# 15_SOLENOID_2.net
KiCad netlist of a schematic drawn in Altium Designer
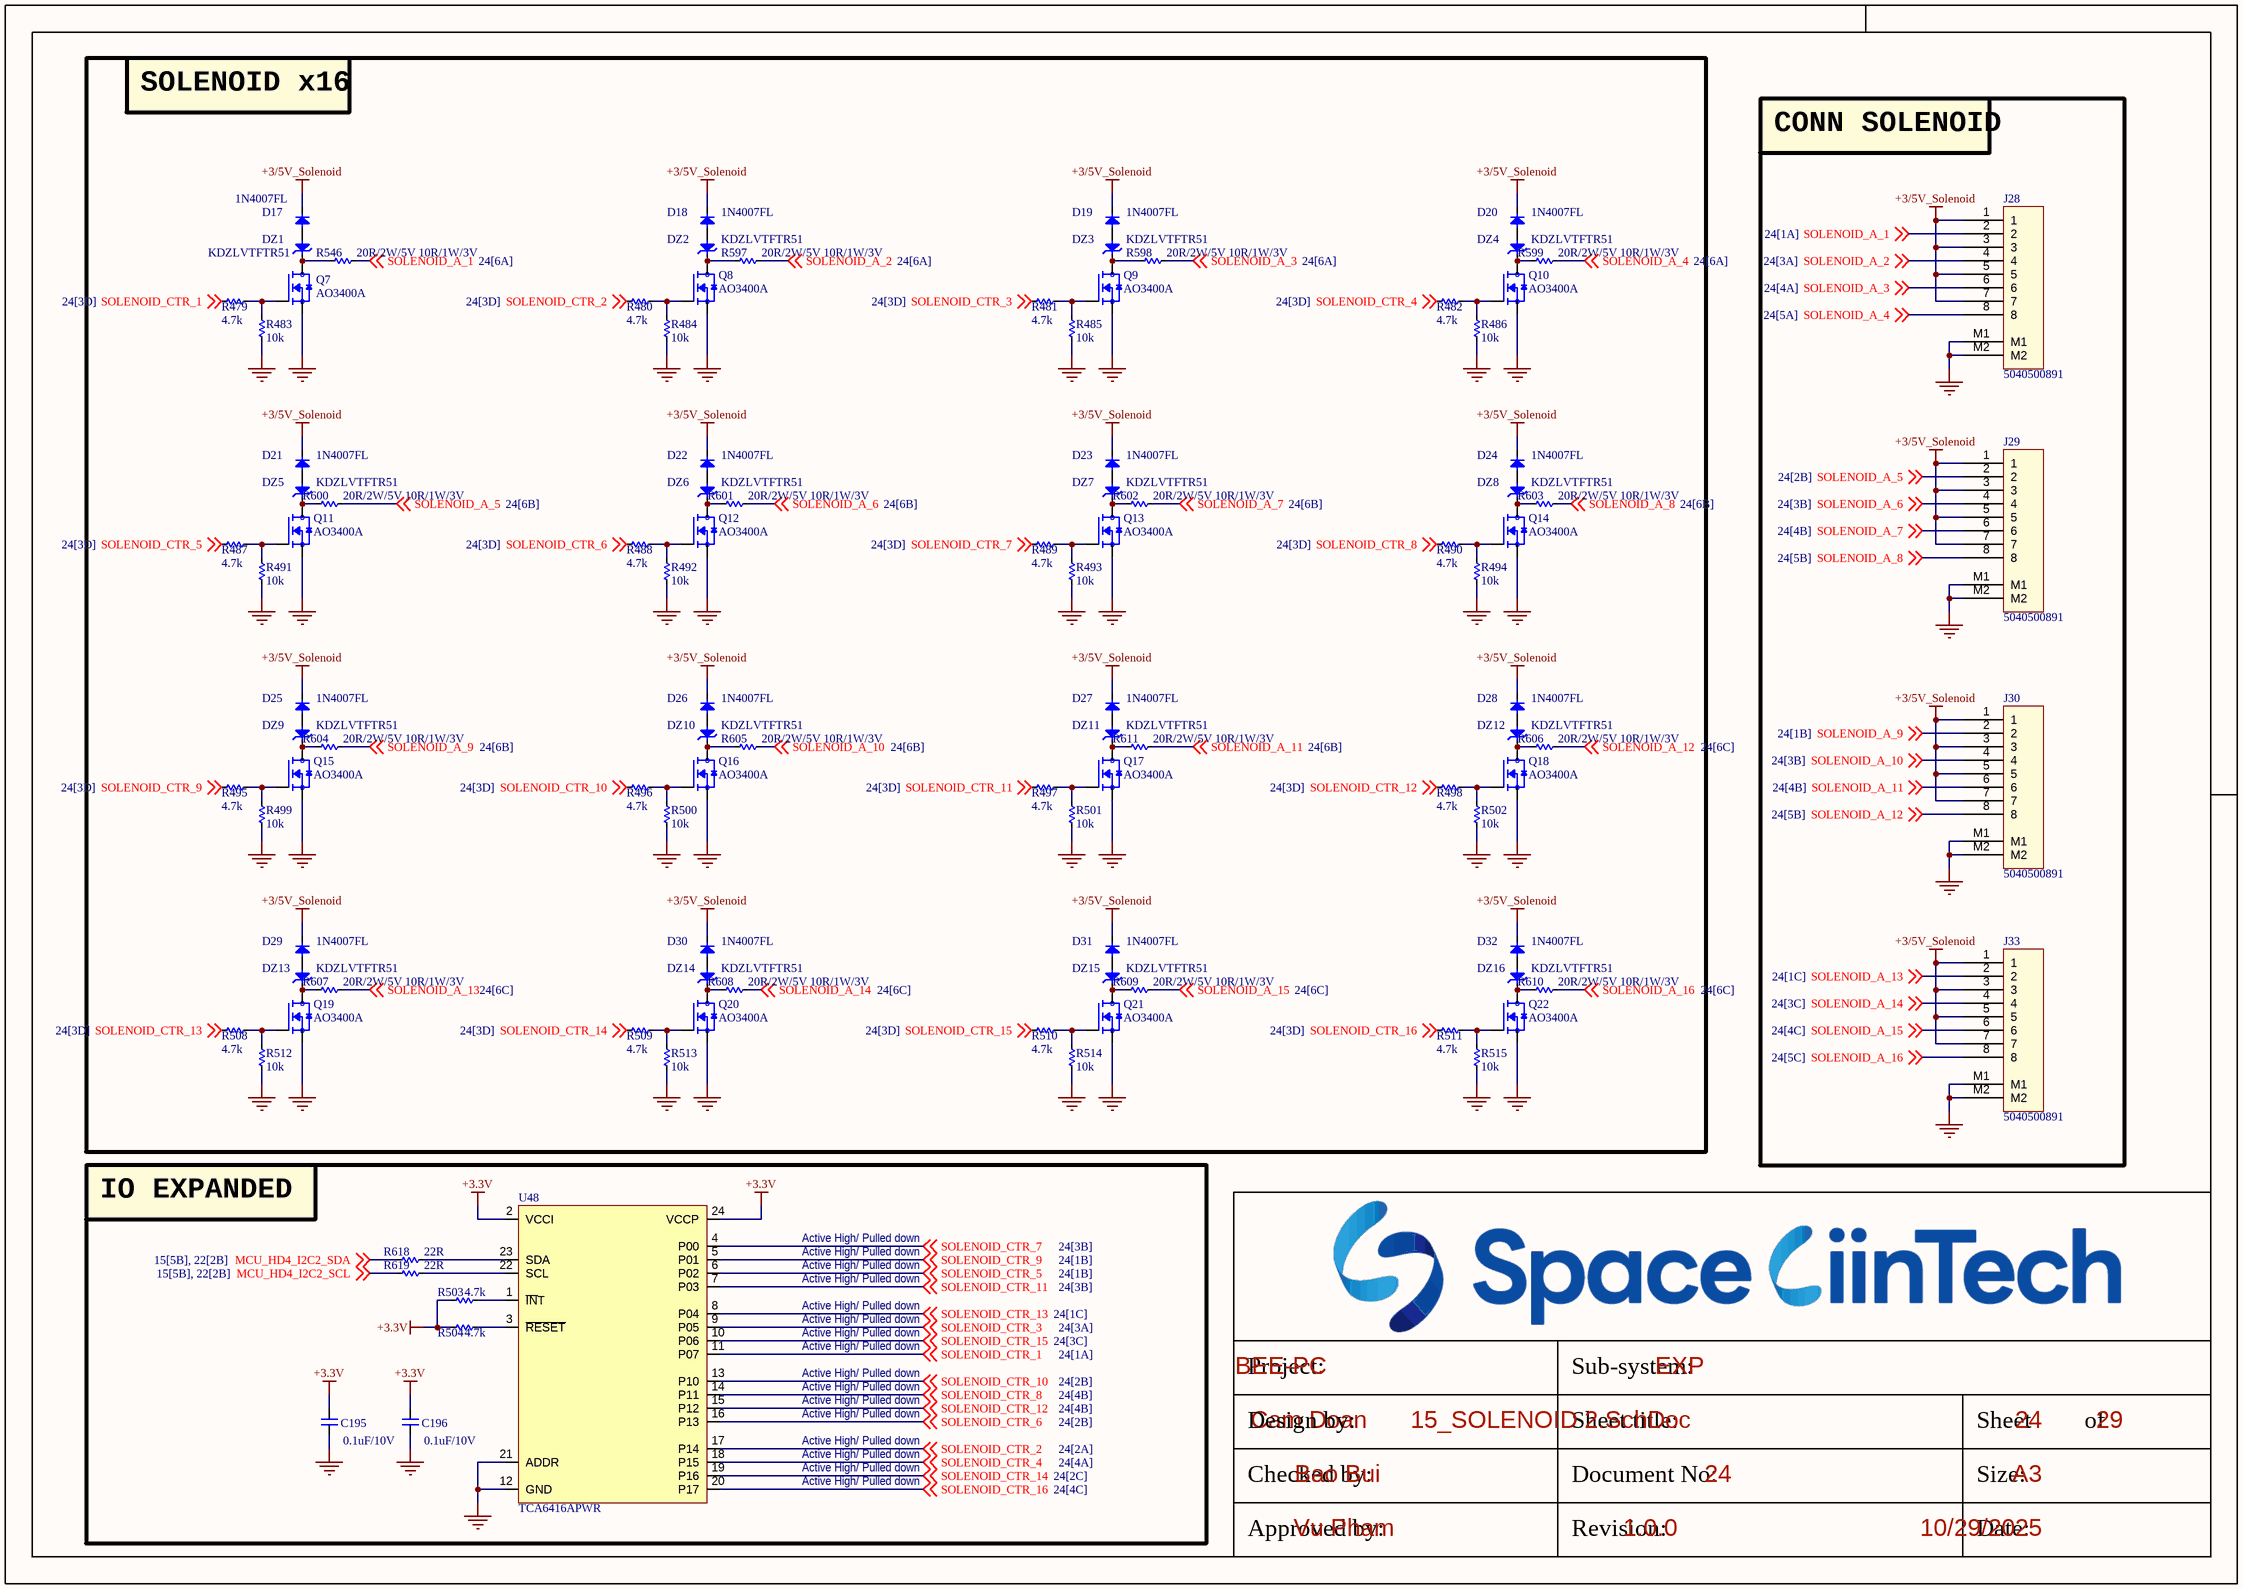
[diagram p0: 15_SOLENOID 2.SchDoc]

(export (version "E")
  (design (tool "Eeschema 10.0.6"))
  (components
    (comp (ref "C195")
      (value "0.1uF/10V")
      (footprint "CAP_C_1005X60")
      (description "CAP CHIP")
      (libsource (lib "LABLIB") (part "_CAP_C_2"))
    )
    (comp (ref "C196")
      (value "0.1uF/10V")
      (footprint "CAP_C_1005X60")
      (description "CAP CHIP")
      (libsource (lib "LABLIB") (part "_CAP_C_2"))
    )
    (comp (ref "D17")
      (value "1N4007FL")
      (footprint "SOD3717X145N")
      (description "Default Diode")
      (fields (field (name "PUBLISHER") "Altium Limited"))
      (libsource (lib "LABLIB") (part "Diode SMD"))
    )
    (comp (ref "D18")
      (value "1N4007FL")
      (footprint "SOD3717X145N")
      (description "Default Diode")
      (fields (field (name "PUBLISHER") "Altium Limited"))
      (libsource (lib "LABLIB") (part "Diode SMD"))
    )
    (comp (ref "D19")
      (value "1N4007FL")
      (footprint "SOD3717X145N")
      (description "Default Diode")
      (fields (field (name "PUBLISHER") "Altium Limited"))
      (libsource (lib "LABLIB") (part "Diode SMD"))
    )
    (comp (ref "D20")
      (value "1N4007FL")
      (footprint "SOD3717X145N")
      (description "Default Diode")
      (fields (field (name "PUBLISHER") "Altium Limited"))
      (libsource (lib "LABLIB") (part "Diode SMD"))
    )
    (comp (ref "D21")
      (value "1N4007FL")
      (footprint "SOD3717X145N")
      (description "Default Diode")
      (fields (field (name "PUBLISHER") "Altium Limited"))
      (libsource (lib "LABLIB") (part "Diode SMD"))
    )
    (comp (ref "D22")
      (value "1N4007FL")
      (footprint "SOD3717X145N")
      (description "Default Diode")
      (fields (field (name "PUBLISHER") "Altium Limited"))
      (libsource (lib "LABLIB") (part "Diode SMD"))
    )
    (comp (ref "D23")
      (value "1N4007FL")
      (footprint "SOD3717X145N")
      (description "Default Diode")
      (fields (field (name "PUBLISHER") "Altium Limited"))
      (libsource (lib "LABLIB") (part "Diode SMD"))
    )
    (comp (ref "D24")
      (value "1N4007FL")
      (footprint "SOD3717X145N")
      (description "Default Diode")
      (fields (field (name "PUBLISHER") "Altium Limited"))
      (libsource (lib "LABLIB") (part "Diode SMD"))
    )
    (comp (ref "D25")
      (value "1N4007FL")
      (footprint "SOD3717X145N")
      (description "Default Diode")
      (fields (field (name "PUBLISHER") "Altium Limited"))
      (libsource (lib "LABLIB") (part "Diode SMD"))
    )
    (comp (ref "D26")
      (value "1N4007FL")
      (footprint "SOD3717X145N")
      (description "Default Diode")
      (fields (field (name "PUBLISHER") "Altium Limited"))
      (libsource (lib "LABLIB") (part "Diode SMD"))
    )
    (comp (ref "D27")
      (value "1N4007FL")
      (footprint "SOD3717X145N")
      (description "Default Diode")
      (fields (field (name "PUBLISHER") "Altium Limited"))
      (libsource (lib "LABLIB") (part "Diode SMD"))
    )
    (comp (ref "D28")
      (value "1N4007FL")
      (footprint "SOD3717X145N")
      (description "Default Diode")
      (fields (field (name "PUBLISHER") "Altium Limited"))
      (libsource (lib "LABLIB") (part "Diode SMD"))
    )
    (comp (ref "D29")
      (value "1N4007FL")
      (footprint "SOD3717X145N")
      (description "Default Diode")
      (fields (field (name "PUBLISHER") "Altium Limited"))
      (libsource (lib "LABLIB") (part "Diode SMD"))
    )
    (comp (ref "D30")
      (value "1N4007FL")
      (footprint "SOD3717X145N")
      (description "Default Diode")
      (fields (field (name "PUBLISHER") "Altium Limited"))
      (libsource (lib "LABLIB") (part "Diode SMD"))
    )
    (comp (ref "D31")
      (value "1N4007FL")
      (footprint "SOD3717X145N")
      (description "Default Diode")
      (fields (field (name "PUBLISHER") "Altium Limited"))
      (libsource (lib "LABLIB") (part "Diode SMD"))
    )
    (comp (ref "D32")
      (value "1N4007FL")
      (footprint "SOD3717X145N")
      (description "Default Diode")
      (fields (field (name "PUBLISHER") "Altium Limited"))
      (libsource (lib "LABLIB") (part "Diode SMD"))
    )
    (comp (ref "DZ1")
      (value "KDZLVTFTR51")
      (footprint "SOD3717X145N")
      (description "Zenner")
      (libsource (lib "LABLIB") (part "DIODE Zener"))
    )
    (comp (ref "DZ2")
      (value "KDZLVTFTR51")
      (footprint "SOD3717X145N")
      (description "Zenner")
      (libsource (lib "LABLIB") (part "DIODE Zener"))
    )
    (comp (ref "DZ3")
      (value "KDZLVTFTR51")
      (footprint "SOD3717X145N")
      (description "Zenner")
      (libsource (lib "LABLIB") (part "DIODE Zener"))
    )
    (comp (ref "DZ4")
      (value "KDZLVTFTR51")
      (footprint "SOD3717X145N")
      (description "Zenner")
      (libsource (lib "LABLIB") (part "DIODE Zener"))
    )
    (comp (ref "DZ5")
      (value "KDZLVTFTR51")
      (footprint "SOD3717X145N")
      (description "Zenner")
      (libsource (lib "LABLIB") (part "DIODE Zener"))
    )
    (comp (ref "DZ6")
      (value "KDZLVTFTR51")
      (footprint "SOD3717X145N")
      (description "Zenner")
      (libsource (lib "LABLIB") (part "DIODE Zener"))
    )
    (comp (ref "DZ7")
      (value "KDZLVTFTR51")
      (footprint "SOD3717X145N")
      (description "Zenner")
      (libsource (lib "LABLIB") (part "DIODE Zener"))
    )
    (comp (ref "DZ8")
      (value "KDZLVTFTR51")
      (footprint "SOD3717X145N")
      (description "Zenner")
      (libsource (lib "LABLIB") (part "DIODE Zener"))
    )
    (comp (ref "DZ9")
      (value "KDZLVTFTR51")
      (footprint "SOD3717X145N")
      (description "Zenner")
      (libsource (lib "LABLIB") (part "DIODE Zener"))
    )
    (comp (ref "DZ10")
      (value "KDZLVTFTR51")
      (footprint "SOD3717X145N")
      (description "Zenner")
      (libsource (lib "LABLIB") (part "DIODE Zener"))
    )
    (comp (ref "DZ11")
      (value "KDZLVTFTR51")
      (footprint "SOD3717X145N")
      (description "Zenner")
      (libsource (lib "LABLIB") (part "DIODE Zener"))
    )
    (comp (ref "DZ12")
      (value "KDZLVTFTR51")
      (footprint "SOD3717X145N")
      (description "Zenner")
      (libsource (lib "LABLIB") (part "DIODE Zener"))
    )
    (comp (ref "DZ13")
      (value "KDZLVTFTR51")
      (footprint "SOD3717X145N")
      (description "Zenner")
      (libsource (lib "LABLIB") (part "DIODE Zener"))
    )
    (comp (ref "DZ14")
      (value "KDZLVTFTR51")
      (footprint "SOD3717X145N")
      (description "Zenner")
      (libsource (lib "LABLIB") (part "DIODE Zener"))
    )
    (comp (ref "DZ15")
      (value "KDZLVTFTR51")
      (footprint "SOD3717X145N")
      (description "Zenner")
      (libsource (lib "LABLIB") (part "DIODE Zener"))
    )
    (comp (ref "DZ16")
      (value "KDZLVTFTR51")
      (footprint "SOD3717X145N")
      (description "Zenner")
      (libsource (lib "LABLIB") (part "DIODE Zener"))
    )
    (comp (ref "J28")
      (value "5040500891")
      (footprint "MOLEX_5040500891")
      (libsource (lib "LABLIB") (part "Header 8x1_2M"))
    )
    (comp (ref "J29")
      (value "5040500891")
      (footprint "MOLEX_5040500891")
      (libsource (lib "LABLIB") (part "Header 8x1_2M"))
    )
    (comp (ref "J30")
      (value "5040500891")
      (footprint "MOLEX_5040500891")
      (libsource (lib "LABLIB") (part "Header 8x1_2M"))
    )
    (comp (ref "J33")
      (value "5040500891")
      (footprint "MOLEX_5040500891")
      (libsource (lib "LABLIB") (part "Header 8x1_2M"))
    )
    (comp (ref "Q7")
      (value "AO3400A")
      (footprint "SOT95P240X120-3N")
      (description "N-Channel 30 V 5.7A (Ta) 1.4W (Ta) Surface Mount SOT-23-3")
      (fields (field (name "MF") "Alpha & Omega Semiconductor"))
      (libsource (lib "new_component") (part "MOSFET_N"))
    )
    (comp (ref "Q8")
      (value "AO3400A")
      (footprint "SOT95P240X120-3N")
      (description "N-Channel 30 V 5.7A (Ta) 1.4W (Ta) Surface Mount SOT-23-3")
      (fields (field (name "MF") "Alpha & Omega Semiconductor"))
      (libsource (lib "new_component") (part "MOSFET_N"))
    )
    (comp (ref "Q9")
      (value "AO3400A")
      (footprint "SOT95P240X120-3N")
      (description "N-Channel 30 V 5.7A (Ta) 1.4W (Ta) Surface Mount SOT-23-3")
      (fields (field (name "MF") "Alpha & Omega Semiconductor"))
      (libsource (lib "new_component") (part "MOSFET_N"))
    )
    (comp (ref "Q10")
      (value "AO3400A")
      (footprint "SOT95P240X120-3N")
      (description "N-Channel 30 V 5.7A (Ta) 1.4W (Ta) Surface Mount SOT-23-3")
      (fields (field (name "MF") "Alpha & Omega Semiconductor"))
      (libsource (lib "new_component") (part "MOSFET_N"))
    )
    (comp (ref "Q11")
      (value "AO3400A")
      (footprint "SOT95P240X120-3N")
      (description "N-Channel 30 V 5.7A (Ta) 1.4W (Ta) Surface Mount SOT-23-3")
      (fields (field (name "MF") "Alpha & Omega Semiconductor"))
      (libsource (lib "new_component") (part "MOSFET_N"))
    )
    (comp (ref "Q12")
      (value "AO3400A")
      (footprint "SOT95P240X120-3N")
      (description "N-Channel 30 V 5.7A (Ta) 1.4W (Ta) Surface Mount SOT-23-3")
      (fields (field (name "MF") "Alpha & Omega Semiconductor"))
      (libsource (lib "new_component") (part "MOSFET_N"))
    )
    (comp (ref "Q13")
      (value "AO3400A")
      (footprint "SOT95P240X120-3N")
      (description "N-Channel 30 V 5.7A (Ta) 1.4W (Ta) Surface Mount SOT-23-3")
      (fields (field (name "MF") "Alpha & Omega Semiconductor"))
      (libsource (lib "new_component") (part "MOSFET_N"))
    )
    (comp (ref "Q14")
      (value "AO3400A")
      (footprint "SOT95P240X120-3N")
      (description "N-Channel 30 V 5.7A (Ta) 1.4W (Ta) Surface Mount SOT-23-3")
      (fields (field (name "MF") "Alpha & Omega Semiconductor"))
      (libsource (lib "new_component") (part "MOSFET_N"))
    )
    (comp (ref "Q15")
      (value "AO3400A")
      (footprint "SOT95P240X120-3N")
      (description "N-Channel 30 V 5.7A (Ta) 1.4W (Ta) Surface Mount SOT-23-3")
      (fields (field (name "MF") "Alpha & Omega Semiconductor"))
      (libsource (lib "new_component") (part "MOSFET_N"))
    )
    (comp (ref "Q16")
      (value "AO3400A")
      (footprint "SOT95P240X120-3N")
      (description "N-Channel 30 V 5.7A (Ta) 1.4W (Ta) Surface Mount SOT-23-3")
      (fields (field (name "MF") "Alpha & Omega Semiconductor"))
      (libsource (lib "new_component") (part "MOSFET_N"))
    )
    (comp (ref "Q17")
      (value "AO3400A")
      (footprint "SOT95P240X120-3N")
      (description "N-Channel 30 V 5.7A (Ta) 1.4W (Ta) Surface Mount SOT-23-3")
      (fields (field (name "MF") "Alpha & Omega Semiconductor"))
      (libsource (lib "new_component") (part "MOSFET_N"))
    )
    (comp (ref "Q18")
      (value "AO3400A")
      (footprint "SOT95P240X120-3N")
      (description "N-Channel 30 V 5.7A (Ta) 1.4W (Ta) Surface Mount SOT-23-3")
      (fields (field (name "MF") "Alpha & Omega Semiconductor"))
      (libsource (lib "new_component") (part "MOSFET_N"))
    )
    (comp (ref "Q19")
      (value "AO3400A")
      (footprint "SOT95P240X120-3N")
      (description "N-Channel 30 V 5.7A (Ta) 1.4W (Ta) Surface Mount SOT-23-3")
      (fields (field (name "MF") "Alpha & Omega Semiconductor"))
      (libsource (lib "new_component") (part "MOSFET_N"))
    )
    (comp (ref "Q20")
      (value "AO3400A")
      (footprint "SOT95P240X120-3N")
      (description "N-Channel 30 V 5.7A (Ta) 1.4W (Ta) Surface Mount SOT-23-3")
      (fields (field (name "MF") "Alpha & Omega Semiconductor"))
      (libsource (lib "new_component") (part "MOSFET_N"))
    )
    (comp (ref "Q21")
      (value "AO3400A")
      (footprint "SOT95P240X120-3N")
      (description "N-Channel 30 V 5.7A (Ta) 1.4W (Ta) Surface Mount SOT-23-3")
      (fields (field (name "MF") "Alpha & Omega Semiconductor"))
      (libsource (lib "new_component") (part "MOSFET_N"))
    )
    (comp (ref "Q22")
      (value "AO3400A")
      (footprint "SOT95P240X120-3N")
      (description "N-Channel 30 V 5.7A (Ta) 1.4W (Ta) Surface Mount SOT-23-3")
      (fields (field (name "MF") "Alpha & Omega Semiconductor"))
      (libsource (lib "new_component") (part "MOSFET_N"))
    )
    (comp (ref "R479")
      (value "4.7k")
      (footprint "RES_C_1005X40")
      (description "RES")
      (libsource (lib "LABLIB") (part "_RES_B_2"))
    )
    (comp (ref "R480")
      (value "4.7k")
      (footprint "RES_C_1005X40")
      (description "RES")
      (libsource (lib "LABLIB") (part "_RES_B_2"))
    )
    (comp (ref "R481")
      (value "4.7k")
      (footprint "RES_C_1005X40")
      (description "RES")
      (libsource (lib "LABLIB") (part "_RES_B_2"))
    )
    (comp (ref "R482")
      (value "4.7k")
      (footprint "RES_C_1005X40")
      (description "RES")
      (libsource (lib "LABLIB") (part "_RES_B_2"))
    )
    (comp (ref "R483")
      (value "10k")
      (footprint "RES_C_1005X40")
      (description "RES")
      (libsource (lib "LABLIB") (part "_RES_B_2"))
    )
    (comp (ref "R484")
      (value "10k")
      (footprint "RES_C_1005X40")
      (description "RES")
      (libsource (lib "LABLIB") (part "_RES_B_2"))
    )
    (comp (ref "R485")
      (value "10k")
      (footprint "RES_C_1005X40")
      (description "RES")
      (libsource (lib "LABLIB") (part "_RES_B_2"))
    )
    (comp (ref "R486")
      (value "10k")
      (footprint "RES_C_1005X40")
      (description "RES")
      (libsource (lib "LABLIB") (part "_RES_B_2"))
    )
    (comp (ref "R487")
      (value "4.7k")
      (footprint "RES_C_1005X40")
      (description "RES")
      (libsource (lib "LABLIB") (part "_RES_B_2"))
    )
    (comp (ref "R488")
      (value "4.7k")
      (footprint "RES_C_1005X40")
      (description "RES")
      (libsource (lib "LABLIB") (part "_RES_B_2"))
    )
    (comp (ref "R489")
      (value "4.7k")
      (footprint "RES_C_1005X40")
      (description "RES")
      (libsource (lib "LABLIB") (part "_RES_B_2"))
    )
    (comp (ref "R490")
      (value "4.7k")
      (footprint "RES_C_1005X40")
      (description "RES")
      (libsource (lib "LABLIB") (part "_RES_B_2"))
    )
    (comp (ref "R491")
      (value "10k")
      (footprint "RES_C_1005X40")
      (description "RES")
      (libsource (lib "LABLIB") (part "_RES_B_2"))
    )
    (comp (ref "R492")
      (value "10k")
      (footprint "RES_C_1005X40")
      (description "RES")
      (libsource (lib "LABLIB") (part "_RES_B_2"))
    )
    (comp (ref "R493")
      (value "10k")
      (footprint "RES_C_1005X40")
      (description "RES")
      (libsource (lib "LABLIB") (part "_RES_B_2"))
    )
    (comp (ref "R494")
      (value "10k")
      (footprint "RES_C_1005X40")
      (description "RES")
      (libsource (lib "LABLIB") (part "_RES_B_2"))
    )
    (comp (ref "R495")
      (value "4.7k")
      (footprint "RES_C_1005X40")
      (description "RES")
      (libsource (lib "LABLIB") (part "_RES_B_2"))
    )
    (comp (ref "R496")
      (value "4.7k")
      (footprint "RES_C_1005X40")
      (description "RES")
      (libsource (lib "LABLIB") (part "_RES_B_2"))
    )
    (comp (ref "R497")
      (value "4.7k")
      (footprint "RES_C_1005X40")
      (description "RES")
      (libsource (lib "LABLIB") (part "_RES_B_2"))
    )
    (comp (ref "R498")
      (value "4.7k")
      (footprint "RES_C_1005X40")
      (description "RES")
      (libsource (lib "LABLIB") (part "_RES_B_2"))
    )
    (comp (ref "R499")
      (value "10k")
      (footprint "RES_C_1005X40")
      (description "RES")
      (libsource (lib "LABLIB") (part "_RES_B_2"))
    )
    (comp (ref "R500")
      (value "10k")
      (footprint "RES_C_1005X40")
      (description "RES")
      (libsource (lib "LABLIB") (part "_RES_B_2"))
    )
    (comp (ref "R501")
      (value "10k")
      (footprint "RES_C_1005X40")
      (description "RES")
      (libsource (lib "LABLIB") (part "_RES_B_2"))
    )
    (comp (ref "R502")
      (value "10k")
      (footprint "RES_C_1005X40")
      (description "RES")
      (libsource (lib "LABLIB") (part "_RES_B_2"))
    )
    (comp (ref "R503")
      (value "4.7k")
      (footprint "RES_C_1005X40")
      (description "RES")
      (libsource (lib "LABLIB") (part "_RES_B_2"))
    )
    (comp (ref "R504")
      (value "4.7k")
      (footprint "RES_C_1005X40")
      (description "RES")
      (libsource (lib "LABLIB") (part "_RES_B_2"))
    )
    (comp (ref "R508")
      (value "4.7k")
      (footprint "RES_C_1005X40")
      (description "RES")
      (libsource (lib "LABLIB") (part "_RES_B_2"))
    )
    (comp (ref "R509")
      (value "4.7k")
      (footprint "RES_C_1005X40")
      (description "RES")
      (libsource (lib "LABLIB") (part "_RES_B_2"))
    )
    (comp (ref "R510")
      (value "4.7k")
      (footprint "RES_C_1005X40")
      (description "RES")
      (libsource (lib "LABLIB") (part "_RES_B_2"))
    )
    (comp (ref "R511")
      (value "4.7k")
      (footprint "RES_C_1005X40")
      (description "RES")
      (libsource (lib "LABLIB") (part "_RES_B_2"))
    )
    (comp (ref "R512")
      (value "10k")
      (footprint "RES_C_1005X40")
      (description "RES")
      (libsource (lib "LABLIB") (part "_RES_B_2"))
    )
    (comp (ref "R513")
      (value "10k")
      (footprint "RES_C_1005X40")
      (description "RES")
      (libsource (lib "LABLIB") (part "_RES_B_2"))
    )
    (comp (ref "R514")
      (value "10k")
      (footprint "RES_C_1005X40")
      (description "RES")
      (libsource (lib "LABLIB") (part "_RES_B_2"))
    )
    (comp (ref "R515")
      (value "10k")
      (footprint "RES_C_1005X40")
      (description "RES")
      (libsource (lib "LABLIB") (part "_RES_B_2"))
    )
    (comp (ref "R546")
      (value "20R/2W/5V 10R/1W/3V")
      (footprint "RES_C_6331X65_N")
      (description "RES")
      (libsource (lib "LABLIB") (part "_RES_B_2"))
    )
    (comp (ref "R597")
      (value "20R/2W/5V 10R/1W/3V")
      (footprint "RES_C_6331X65_N")
      (description "RES")
      (libsource (lib "LABLIB") (part "_RES_B_2"))
    )
    (comp (ref "R598")
      (value "20R/2W/5V 10R/1W/3V")
      (footprint "RES_C_6331X65_N")
      (description "RES")
      (libsource (lib "LABLIB") (part "_RES_B_2"))
    )
    (comp (ref "R599")
      (value "20R/2W/5V 10R/1W/3V")
      (footprint "RES_C_6331X65_N")
      (description "RES")
      (libsource (lib "LABLIB") (part "_RES_B_2"))
    )
    (comp (ref "R600")
      (value "20R/2W/5V 10R/1W/3V")
      (footprint "RES_C_6331X65_N")
      (description "RES")
      (libsource (lib "LABLIB") (part "_RES_B_2"))
    )
    (comp (ref "R601")
      (value "20R/2W/5V 10R/1W/3V")
      (footprint "RES_C_6331X65_N")
      (description "RES")
      (libsource (lib "LABLIB") (part "_RES_B_2"))
    )
    (comp (ref "R602")
      (value "20R/2W/5V 10R/1W/3V")
      (footprint "RES_C_6331X65_N")
      (description "RES")
      (libsource (lib "LABLIB") (part "_RES_B_2"))
    )
    (comp (ref "R603")
      (value "20R/2W/5V 10R/1W/3V")
      (footprint "RES_C_6331X65_N")
      (description "RES")
      (libsource (lib "LABLIB") (part "_RES_B_2"))
    )
    (comp (ref "R604")
      (value "20R/2W/5V 10R/1W/3V")
      (footprint "RES_C_6331X65_N")
      (description "RES")
      (libsource (lib "LABLIB") (part "_RES_B_2"))
    )
    (comp (ref "R605")
      (value "20R/2W/5V 10R/1W/3V")
      (footprint "RES_C_6331X65_N")
      (description "RES")
      (libsource (lib "LABLIB") (part "_RES_B_2"))
    )
    (comp (ref "R606")
      (value "20R/2W/5V 10R/1W/3V")
      (footprint "RES_C_6331X65_N")
      (description "RES")
      (libsource (lib "LABLIB") (part "_RES_B_2"))
    )
    (comp (ref "R607")
      (value "20R/2W/5V 10R/1W/3V")
      (footprint "RES_C_6331X65_N")
      (description "RES")
      (libsource (lib "LABLIB") (part "_RES_B_2"))
    )
    (comp (ref "R608")
      (value "20R/2W/5V 10R/1W/3V")
      (footprint "RES_C_6331X65_N")
      (description "RES")
      (libsource (lib "LABLIB") (part "_RES_B_2"))
    )
    (comp (ref "R609")
      (value "20R/2W/5V 10R/1W/3V")
      (footprint "RES_C_6331X65_N")
      (description "RES")
      (libsource (lib "LABLIB") (part "_RES_B_2"))
    )
    (comp (ref "R610")
      (value "20R/2W/5V 10R/1W/3V")
      (footprint "RES_C_6331X65_N")
      (description "RES")
      (libsource (lib "LABLIB") (part "_RES_B_2"))
    )
    (comp (ref "R611")
      (value "20R/2W/5V 10R/1W/3V")
      (footprint "RES_C_6331X65_N")
      (description "RES")
      (libsource (lib "LABLIB") (part "_RES_B_2"))
    )
    (comp (ref "R618")
      (value "22R")
      (footprint "RES_C_1005X40")
      (description "RES")
      (libsource (lib "LABLIB") (part "_RES_B_2"))
    )
    (comp (ref "R619")
      (value "22R")
      (footprint "RES_C_1005X40")
      (description "RES")
      (libsource (lib "LABLIB") (part "_RES_B_2"))
    )
    (comp (ref "U48")
      (value "TCA6416APWR")
      (footprint "SOP65P440W-24N")
      (libsource (lib "CAMERA_SchLib") (part "IC_I2Cto16IO_TCA6416APWR"))
    )
  )
  (nets
    (net (code "1") (name "+3.3V") (class "Default")
      (node (ref "C195") (pin "2") (pinfunction "2_2") (pintype "passive"))
      (node (ref "C196") (pin "2") (pinfunction "2_2") (pintype "passive"))
      (node (ref "R503") (pin "1") (pinfunction "1_1") (pintype "passive"))
      (node (ref "R504") (pin "1") (pinfunction "1_1") (pintype "passive"))
      (node (ref "U48") (pin "2") (pinfunction "VCCI_2") (pintype "passive"))
      (node (ref "U48") (pin "24") (pinfunction "VCCP_24") (pintype "passive"))
    )
    (net (code "2") (name "+3{slash}5V_Solenoid") (class "Default")
      (node (ref "D17") (pin "1") (pinfunction "K_1") (pintype "passive"))
      (node (ref "D18") (pin "1") (pinfunction "K_1") (pintype "passive"))
      (node (ref "D19") (pin "1") (pinfunction "K_1") (pintype "passive"))
      (node (ref "D20") (pin "1") (pinfunction "K_1") (pintype "passive"))
      (node (ref "D21") (pin "1") (pinfunction "K_1") (pintype "passive"))
      (node (ref "D22") (pin "1") (pinfunction "K_1") (pintype "passive"))
      (node (ref "D23") (pin "1") (pinfunction "K_1") (pintype "passive"))
      (node (ref "D24") (pin "1") (pinfunction "K_1") (pintype "passive"))
      (node (ref "D25") (pin "1") (pinfunction "K_1") (pintype "passive"))
      (node (ref "D26") (pin "1") (pinfunction "K_1") (pintype "passive"))
      (node (ref "D27") (pin "1") (pinfunction "K_1") (pintype "passive"))
      (node (ref "D28") (pin "1") (pinfunction "K_1") (pintype "passive"))
      (node (ref "D29") (pin "1") (pinfunction "K_1") (pintype "passive"))
      (node (ref "D30") (pin "1") (pinfunction "K_1") (pintype "passive"))
      (node (ref "D31") (pin "1") (pinfunction "K_1") (pintype "passive"))
      (node (ref "D32") (pin "1") (pinfunction "K_1") (pintype "passive"))
      (node (ref "J28") (pin "1") (pinfunction "1_1") (pintype "passive"))
      (node (ref "J28") (pin "3") (pinfunction "3_3") (pintype "passive"))
      (node (ref "J28") (pin "5") (pinfunction "5_5") (pintype "passive"))
      (node (ref "J28") (pin "7") (pinfunction "7_7") (pintype "passive"))
      (node (ref "J29") (pin "1") (pinfunction "1_1") (pintype "passive"))
      (node (ref "J29") (pin "3") (pinfunction "3_3") (pintype "passive"))
      (node (ref "J29") (pin "5") (pinfunction "5_5") (pintype "passive"))
      (node (ref "J29") (pin "7") (pinfunction "7_7") (pintype "passive"))
      (node (ref "J30") (pin "1") (pinfunction "1_1") (pintype "passive"))
      (node (ref "J30") (pin "3") (pinfunction "3_3") (pintype "passive"))
      (node (ref "J30") (pin "5") (pinfunction "5_5") (pintype "passive"))
      (node (ref "J30") (pin "7") (pinfunction "7_7") (pintype "passive"))
      (node (ref "J33") (pin "1") (pinfunction "1_1") (pintype "passive"))
      (node (ref "J33") (pin "3") (pinfunction "3_3") (pintype "passive"))
      (node (ref "J33") (pin "5") (pinfunction "5_5") (pintype "passive"))
      (node (ref "J33") (pin "7") (pinfunction "7_7") (pintype "passive"))
    )
    (net (code "3") (name "GND") (class "Default")
      (node (ref "C195") (pin "1") (pinfunction "1_1") (pintype "passive"))
      (node (ref "C196") (pin "1") (pinfunction "1_1") (pintype "passive"))
      (node (ref "J28") (pin "M1") (pinfunction "M1_M1") (pintype "passive"))
      (node (ref "J28") (pin "M2") (pinfunction "M2_M2") (pintype "passive"))
      (node (ref "J29") (pin "M1") (pinfunction "M1_M1") (pintype "passive"))
      (node (ref "J29") (pin "M2") (pinfunction "M2_M2") (pintype "passive"))
      (node (ref "J30") (pin "M1") (pinfunction "M1_M1") (pintype "passive"))
      (node (ref "J30") (pin "M2") (pinfunction "M2_M2") (pintype "passive"))
      (node (ref "J33") (pin "M1") (pinfunction "M1_M1") (pintype "passive"))
      (node (ref "J33") (pin "M2") (pinfunction "M2_M2") (pintype "passive"))
      (node (ref "Q10") (pin "2") (pinfunction "S_2") (pintype "passive"))
      (node (ref "Q11") (pin "2") (pinfunction "S_2") (pintype "passive"))
      (node (ref "Q12") (pin "2") (pinfunction "S_2") (pintype "passive"))
      (node (ref "Q13") (pin "2") (pinfunction "S_2") (pintype "passive"))
      (node (ref "Q14") (pin "2") (pinfunction "S_2") (pintype "passive"))
      (node (ref "Q15") (pin "2") (pinfunction "S_2") (pintype "passive"))
      (node (ref "Q16") (pin "2") (pinfunction "S_2") (pintype "passive"))
      (node (ref "Q17") (pin "2") (pinfunction "S_2") (pintype "passive"))
      (node (ref "Q18") (pin "2") (pinfunction "S_2") (pintype "passive"))
      (node (ref "Q19") (pin "2") (pinfunction "S_2") (pintype "passive"))
      (node (ref "Q20") (pin "2") (pinfunction "S_2") (pintype "passive"))
      (node (ref "Q21") (pin "2") (pinfunction "S_2") (pintype "passive"))
      (node (ref "Q22") (pin "2") (pinfunction "S_2") (pintype "passive"))
      (node (ref "Q7") (pin "2") (pinfunction "S_2") (pintype "passive"))
      (node (ref "Q8") (pin "2") (pinfunction "S_2") (pintype "passive"))
      (node (ref "Q9") (pin "2") (pinfunction "S_2") (pintype "passive"))
      (node (ref "R483") (pin "1") (pinfunction "1_1") (pintype "passive"))
      (node (ref "R484") (pin "1") (pinfunction "1_1") (pintype "passive"))
      (node (ref "R485") (pin "1") (pinfunction "1_1") (pintype "passive"))
      (node (ref "R486") (pin "1") (pinfunction "1_1") (pintype "passive"))
      (node (ref "R491") (pin "1") (pinfunction "1_1") (pintype "passive"))
      (node (ref "R492") (pin "1") (pinfunction "1_1") (pintype "passive"))
      (node (ref "R493") (pin "1") (pinfunction "1_1") (pintype "passive"))
      (node (ref "R494") (pin "1") (pinfunction "1_1") (pintype "passive"))
      (node (ref "R499") (pin "1") (pinfunction "1_1") (pintype "passive"))
      (node (ref "R500") (pin "1") (pinfunction "1_1") (pintype "passive"))
      (node (ref "R501") (pin "1") (pinfunction "1_1") (pintype "passive"))
      (node (ref "R502") (pin "1") (pinfunction "1_1") (pintype "passive"))
      (node (ref "R512") (pin "1") (pinfunction "1_1") (pintype "passive"))
      (node (ref "R513") (pin "1") (pinfunction "1_1") (pintype "passive"))
      (node (ref "R514") (pin "1") (pinfunction "1_1") (pintype "passive"))
      (node (ref "R515") (pin "1") (pinfunction "1_1") (pintype "passive"))
      (node (ref "U48") (pin "12") (pinfunction "GND_12") (pintype "passive"))
      (node (ref "U48") (pin "21") (pinfunction "ADDR_21") (pintype "passive"))
    )
    (net (code "4") (name "MCU_HD4_I2C2_SCL") (class "Default")
      (node (ref "R619") (pin "2") (pinfunction "2_2") (pintype "passive"))
    )
    (net (code "5") (name "MCU_HD4_I2C2_SDA") (class "Default")
      (node (ref "R618") (pin "2") (pinfunction "2_2") (pintype "passive"))
    )
    (net (code "6") (name "Net-(D17-A)") (class "Default")
      (node (ref "D17") (pin "2") (pinfunction "A_2") (pintype "passive"))
      (node (ref "DZ1") (pin "2") (pinfunction "A_2") (pintype "passive"))
    )
    (net (code "7") (name "Net-(D18-A)") (class "Default")
      (node (ref "D18") (pin "2") (pinfunction "A_2") (pintype "passive"))
      (node (ref "DZ2") (pin "2") (pinfunction "A_2") (pintype "passive"))
    )
    (net (code "8") (name "Net-(D19-A)") (class "Default")
      (node (ref "D19") (pin "2") (pinfunction "A_2") (pintype "passive"))
      (node (ref "DZ3") (pin "2") (pinfunction "A_2") (pintype "passive"))
    )
    (net (code "9") (name "Net-(D20-A)") (class "Default")
      (node (ref "D20") (pin "2") (pinfunction "A_2") (pintype "passive"))
      (node (ref "DZ4") (pin "2") (pinfunction "A_2") (pintype "passive"))
    )
    (net (code "10") (name "Net-(D21-A)") (class "Default")
      (node (ref "D21") (pin "2") (pinfunction "A_2") (pintype "passive"))
      (node (ref "DZ5") (pin "2") (pinfunction "A_2") (pintype "passive"))
    )
    (net (code "11") (name "Net-(D22-A)") (class "Default")
      (node (ref "D22") (pin "2") (pinfunction "A_2") (pintype "passive"))
      (node (ref "DZ6") (pin "2") (pinfunction "A_2") (pintype "passive"))
    )
    (net (code "12") (name "Net-(D23-A)") (class "Default")
      (node (ref "D23") (pin "2") (pinfunction "A_2") (pintype "passive"))
      (node (ref "DZ7") (pin "2") (pinfunction "A_2") (pintype "passive"))
    )
    (net (code "13") (name "Net-(D24-A)") (class "Default")
      (node (ref "D24") (pin "2") (pinfunction "A_2") (pintype "passive"))
      (node (ref "DZ8") (pin "2") (pinfunction "A_2") (pintype "passive"))
    )
    (net (code "14") (name "Net-(D25-A)") (class "Default")
      (node (ref "D25") (pin "2") (pinfunction "A_2") (pintype "passive"))
      (node (ref "DZ9") (pin "2") (pinfunction "A_2") (pintype "passive"))
    )
    (net (code "15") (name "Net-(D26-A)") (class "Default")
      (node (ref "D26") (pin "2") (pinfunction "A_2") (pintype "passive"))
      (node (ref "DZ10") (pin "2") (pinfunction "A_2") (pintype "passive"))
    )
    (net (code "16") (name "Net-(D27-A)") (class "Default")
      (node (ref "D27") (pin "2") (pinfunction "A_2") (pintype "passive"))
      (node (ref "DZ11") (pin "2") (pinfunction "A_2") (pintype "passive"))
    )
    (net (code "17") (name "Net-(D28-A)") (class "Default")
      (node (ref "D28") (pin "2") (pinfunction "A_2") (pintype "passive"))
      (node (ref "DZ12") (pin "2") (pinfunction "A_2") (pintype "passive"))
    )
    (net (code "18") (name "Net-(D29-A)") (class "Default")
      (node (ref "D29") (pin "2") (pinfunction "A_2") (pintype "passive"))
      (node (ref "DZ13") (pin "2") (pinfunction "A_2") (pintype "passive"))
    )
    (net (code "19") (name "Net-(D30-A)") (class "Default")
      (node (ref "D30") (pin "2") (pinfunction "A_2") (pintype "passive"))
      (node (ref "DZ14") (pin "2") (pinfunction "A_2") (pintype "passive"))
    )
    (net (code "20") (name "Net-(D31-A)") (class "Default")
      (node (ref "D31") (pin "2") (pinfunction "A_2") (pintype "passive"))
      (node (ref "DZ15") (pin "2") (pinfunction "A_2") (pintype "passive"))
    )
    (net (code "21") (name "Net-(D32-A)") (class "Default")
      (node (ref "D32") (pin "2") (pinfunction "A_2") (pintype "passive"))
      (node (ref "DZ16") (pin "2") (pinfunction "A_2") (pintype "passive"))
    )
    (net (code "22") (name "Net-(DZ1-K)") (class "Default")
      (node (ref "DZ1") (pin "1") (pinfunction "K_1") (pintype "passive"))
      (node (ref "Q7") (pin "3") (pinfunction "D_3") (pintype "passive"))
      (node (ref "R546") (pin "2") (pinfunction "2_2") (pintype "passive"))
    )
    (net (code "23") (name "Net-(DZ2-K)") (class "Default")
      (node (ref "DZ2") (pin "1") (pinfunction "K_1") (pintype "passive"))
      (node (ref "Q8") (pin "3") (pinfunction "D_3") (pintype "passive"))
      (node (ref "R597") (pin "2") (pinfunction "2_2") (pintype "passive"))
    )
    (net (code "24") (name "Net-(DZ3-K)") (class "Default")
      (node (ref "DZ3") (pin "1") (pinfunction "K_1") (pintype "passive"))
      (node (ref "Q9") (pin "3") (pinfunction "D_3") (pintype "passive"))
      (node (ref "R598") (pin "2") (pinfunction "2_2") (pintype "passive"))
    )
    (net (code "25") (name "Net-(DZ4-K)") (class "Default")
      (node (ref "DZ4") (pin "1") (pinfunction "K_1") (pintype "passive"))
      (node (ref "Q10") (pin "3") (pinfunction "D_3") (pintype "passive"))
      (node (ref "R599") (pin "2") (pinfunction "2_2") (pintype "passive"))
    )
    (net (code "26") (name "Net-(DZ5-K)") (class "Default")
      (node (ref "DZ5") (pin "1") (pinfunction "K_1") (pintype "passive"))
      (node (ref "Q11") (pin "3") (pinfunction "D_3") (pintype "passive"))
      (node (ref "R600") (pin "2") (pinfunction "2_2") (pintype "passive"))
    )
    (net (code "27") (name "Net-(DZ6-K)") (class "Default")
      (node (ref "DZ6") (pin "1") (pinfunction "K_1") (pintype "passive"))
      (node (ref "Q12") (pin "3") (pinfunction "D_3") (pintype "passive"))
      (node (ref "R601") (pin "2") (pinfunction "2_2") (pintype "passive"))
    )
    (net (code "28") (name "Net-(DZ7-K)") (class "Default")
      (node (ref "DZ7") (pin "1") (pinfunction "K_1") (pintype "passive"))
      (node (ref "Q13") (pin "3") (pinfunction "D_3") (pintype "passive"))
      (node (ref "R602") (pin "2") (pinfunction "2_2") (pintype "passive"))
    )
    (net (code "29") (name "Net-(DZ8-K)") (class "Default")
      (node (ref "DZ8") (pin "1") (pinfunction "K_1") (pintype "passive"))
      (node (ref "Q14") (pin "3") (pinfunction "D_3") (pintype "passive"))
      (node (ref "R603") (pin "2") (pinfunction "2_2") (pintype "passive"))
    )
    (net (code "30") (name "Net-(DZ9-K)") (class "Default")
      (node (ref "DZ9") (pin "1") (pinfunction "K_1") (pintype "passive"))
      (node (ref "Q15") (pin "3") (pinfunction "D_3") (pintype "passive"))
      (node (ref "R604") (pin "2") (pinfunction "2_2") (pintype "passive"))
    )
    (net (code "31") (name "Net-(DZ10-K)") (class "Default")
      (node (ref "DZ10") (pin "1") (pinfunction "K_1") (pintype "passive"))
      (node (ref "Q16") (pin "3") (pinfunction "D_3") (pintype "passive"))
      (node (ref "R605") (pin "2") (pinfunction "2_2") (pintype "passive"))
    )
    (net (code "32") (name "Net-(DZ11-K)") (class "Default")
      (node (ref "DZ11") (pin "1") (pinfunction "K_1") (pintype "passive"))
      (node (ref "Q17") (pin "3") (pinfunction "D_3") (pintype "passive"))
      (node (ref "R611") (pin "2") (pinfunction "2_2") (pintype "passive"))
    )
    (net (code "33") (name "Net-(DZ12-K)") (class "Default")
      (node (ref "DZ12") (pin "1") (pinfunction "K_1") (pintype "passive"))
      (node (ref "Q18") (pin "3") (pinfunction "D_3") (pintype "passive"))
      (node (ref "R606") (pin "2") (pinfunction "2_2") (pintype "passive"))
    )
    (net (code "34") (name "Net-(DZ13-K)") (class "Default")
      (node (ref "DZ13") (pin "1") (pinfunction "K_1") (pintype "passive"))
      (node (ref "Q19") (pin "3") (pinfunction "D_3") (pintype "passive"))
      (node (ref "R607") (pin "2") (pinfunction "2_2") (pintype "passive"))
    )
    (net (code "35") (name "Net-(DZ14-K)") (class "Default")
      (node (ref "DZ14") (pin "1") (pinfunction "K_1") (pintype "passive"))
      (node (ref "Q20") (pin "3") (pinfunction "D_3") (pintype "passive"))
      (node (ref "R608") (pin "2") (pinfunction "2_2") (pintype "passive"))
    )
    (net (code "36") (name "Net-(DZ15-K)") (class "Default")
      (node (ref "DZ15") (pin "1") (pinfunction "K_1") (pintype "passive"))
      (node (ref "Q21") (pin "3") (pinfunction "D_3") (pintype "passive"))
      (node (ref "R609") (pin "2") (pinfunction "2_2") (pintype "passive"))
    )
    (net (code "37") (name "Net-(DZ16-K)") (class "Default")
      (node (ref "DZ16") (pin "1") (pinfunction "K_1") (pintype "passive"))
      (node (ref "Q22") (pin "3") (pinfunction "D_3") (pintype "passive"))
      (node (ref "R610") (pin "2") (pinfunction "2_2") (pintype "passive"))
    )
    (net (code "38") (name "Net-(Q7-G)") (class "Default")
      (node (ref "Q7") (pin "1") (pinfunction "G_1") (pintype "passive"))
      (node (ref "R479") (pin "1") (pinfunction "1_1") (pintype "passive"))
      (node (ref "R483") (pin "2") (pinfunction "2_2") (pintype "passive"))
    )
    (net (code "39") (name "Net-(Q8-G)") (class "Default")
      (node (ref "Q8") (pin "1") (pinfunction "G_1") (pintype "passive"))
      (node (ref "R480") (pin "1") (pinfunction "1_1") (pintype "passive"))
      (node (ref "R484") (pin "2") (pinfunction "2_2") (pintype "passive"))
    )
    (net (code "40") (name "Net-(Q9-G)") (class "Default")
      (node (ref "Q9") (pin "1") (pinfunction "G_1") (pintype "passive"))
      (node (ref "R481") (pin "1") (pinfunction "1_1") (pintype "passive"))
      (node (ref "R485") (pin "2") (pinfunction "2_2") (pintype "passive"))
    )
    (net (code "41") (name "Net-(Q10-G)") (class "Default")
      (node (ref "Q10") (pin "1") (pinfunction "G_1") (pintype "passive"))
      (node (ref "R482") (pin "1") (pinfunction "1_1") (pintype "passive"))
      (node (ref "R486") (pin "2") (pinfunction "2_2") (pintype "passive"))
    )
    (net (code "42") (name "Net-(Q11-G)") (class "Default")
      (node (ref "Q11") (pin "1") (pinfunction "G_1") (pintype "passive"))
      (node (ref "R487") (pin "1") (pinfunction "1_1") (pintype "passive"))
      (node (ref "R491") (pin "2") (pinfunction "2_2") (pintype "passive"))
    )
    (net (code "43") (name "Net-(Q12-G)") (class "Default")
      (node (ref "Q12") (pin "1") (pinfunction "G_1") (pintype "passive"))
      (node (ref "R488") (pin "1") (pinfunction "1_1") (pintype "passive"))
      (node (ref "R492") (pin "2") (pinfunction "2_2") (pintype "passive"))
    )
    (net (code "44") (name "Net-(Q13-G)") (class "Default")
      (node (ref "Q13") (pin "1") (pinfunction "G_1") (pintype "passive"))
      (node (ref "R489") (pin "1") (pinfunction "1_1") (pintype "passive"))
      (node (ref "R493") (pin "2") (pinfunction "2_2") (pintype "passive"))
    )
    (net (code "45") (name "Net-(Q14-G)") (class "Default")
      (node (ref "Q14") (pin "1") (pinfunction "G_1") (pintype "passive"))
      (node (ref "R490") (pin "1") (pinfunction "1_1") (pintype "passive"))
      (node (ref "R494") (pin "2") (pinfunction "2_2") (pintype "passive"))
    )
    (net (code "46") (name "Net-(Q15-G)") (class "Default")
      (node (ref "Q15") (pin "1") (pinfunction "G_1") (pintype "passive"))
      (node (ref "R495") (pin "1") (pinfunction "1_1") (pintype "passive"))
      (node (ref "R499") (pin "2") (pinfunction "2_2") (pintype "passive"))
    )
    (net (code "47") (name "Net-(Q16-G)") (class "Default")
      (node (ref "Q16") (pin "1") (pinfunction "G_1") (pintype "passive"))
      (node (ref "R496") (pin "1") (pinfunction "1_1") (pintype "passive"))
      (node (ref "R500") (pin "2") (pinfunction "2_2") (pintype "passive"))
    )
    (net (code "48") (name "Net-(Q17-G)") (class "Default")
      (node (ref "Q17") (pin "1") (pinfunction "G_1") (pintype "passive"))
      (node (ref "R497") (pin "1") (pinfunction "1_1") (pintype "passive"))
      (node (ref "R501") (pin "2") (pinfunction "2_2") (pintype "passive"))
    )
    (net (code "49") (name "Net-(Q18-G)") (class "Default")
      (node (ref "Q18") (pin "1") (pinfunction "G_1") (pintype "passive"))
      (node (ref "R498") (pin "1") (pinfunction "1_1") (pintype "passive"))
      (node (ref "R502") (pin "2") (pinfunction "2_2") (pintype "passive"))
    )
    (net (code "50") (name "Net-(Q19-G)") (class "Default")
      (node (ref "Q19") (pin "1") (pinfunction "G_1") (pintype "passive"))
      (node (ref "R508") (pin "1") (pinfunction "1_1") (pintype "passive"))
      (node (ref "R512") (pin "2") (pinfunction "2_2") (pintype "passive"))
    )
    (net (code "51") (name "Net-(Q20-G)") (class "Default")
      (node (ref "Q20") (pin "1") (pinfunction "G_1") (pintype "passive"))
      (node (ref "R509") (pin "1") (pinfunction "1_1") (pintype "passive"))
      (node (ref "R513") (pin "2") (pinfunction "2_2") (pintype "passive"))
    )
    (net (code "52") (name "Net-(Q21-G)") (class "Default")
      (node (ref "Q21") (pin "1") (pinfunction "G_1") (pintype "passive"))
      (node (ref "R510") (pin "1") (pinfunction "1_1") (pintype "passive"))
      (node (ref "R514") (pin "2") (pinfunction "2_2") (pintype "passive"))
    )
    (net (code "53") (name "Net-(Q22-G)") (class "Default")
      (node (ref "Q22") (pin "1") (pinfunction "G_1") (pintype "passive"))
      (node (ref "R511") (pin "1") (pinfunction "1_1") (pintype "passive"))
      (node (ref "R515") (pin "2") (pinfunction "2_2") (pintype "passive"))
    )
    (net (code "54") (name "Net-(U48-SCL)") (class "Default")
      (node (ref "R619") (pin "1") (pinfunction "1_1") (pintype "passive"))
      (node (ref "U48") (pin "22") (pinfunction "SCL_22") (pintype "passive"))
    )
    (net (code "55") (name "Net-(U48-SDA)") (class "Default")
      (node (ref "R618") (pin "1") (pinfunction "1_1") (pintype "passive"))
      (node (ref "U48") (pin "23") (pinfunction "SDA_23") (pintype "passive"))
    )
    (net (code "56") (name "Net-(U48-~{IN}T)") (class "Default")
      (node (ref "R503") (pin "2") (pinfunction "2_2") (pintype "passive"))
      (node (ref "U48") (pin "1") (pinfunction "~{IN}T_1") (pintype "passive"))
    )
    (net (code "57") (name "Net-(U48-~{RESET})") (class "Default")
      (node (ref "R504") (pin "2") (pinfunction "2_2") (pintype "passive"))
      (node (ref "U48") (pin "3") (pinfunction "~{RESET}_3") (pintype "passive"))
    )
    (net (code "58") (name "SOLENOID_A_1") (class "Default")
      (node (ref "J28") (pin "2") (pinfunction "2_2") (pintype "passive"))
      (node (ref "R546") (pin "1") (pinfunction "1_1") (pintype "passive"))
    )
    (net (code "59") (name "SOLENOID_A_2") (class "Default")
      (node (ref "J28") (pin "4") (pinfunction "4_4") (pintype "passive"))
      (node (ref "R597") (pin "1") (pinfunction "1_1") (pintype "passive"))
    )
    (net (code "60") (name "SOLENOID_A_3") (class "Default")
      (node (ref "J28") (pin "6") (pinfunction "6_6") (pintype "passive"))
      (node (ref "R598") (pin "1") (pinfunction "1_1") (pintype "passive"))
    )
    (net (code "61") (name "SOLENOID_A_4") (class "Default")
      (node (ref "J28") (pin "8") (pinfunction "8_8") (pintype "passive"))
      (node (ref "R599") (pin "1") (pinfunction "1_1") (pintype "passive"))
    )
    (net (code "62") (name "SOLENOID_A_5") (class "Default")
      (node (ref "J29") (pin "2") (pinfunction "2_2") (pintype "passive"))
      (node (ref "R600") (pin "1") (pinfunction "1_1") (pintype "passive"))
    )
    (net (code "63") (name "SOLENOID_A_6") (class "Default")
      (node (ref "J29") (pin "4") (pinfunction "4_4") (pintype "passive"))
      (node (ref "R601") (pin "1") (pinfunction "1_1") (pintype "passive"))
    )
    (net (code "64") (name "SOLENOID_A_7") (class "Default")
      (node (ref "J29") (pin "6") (pinfunction "6_6") (pintype "passive"))
      (node (ref "R602") (pin "1") (pinfunction "1_1") (pintype "passive"))
    )
    (net (code "65") (name "SOLENOID_A_8") (class "Default")
      (node (ref "J29") (pin "8") (pinfunction "8_8") (pintype "passive"))
      (node (ref "R603") (pin "1") (pinfunction "1_1") (pintype "passive"))
    )
    (net (code "66") (name "SOLENOID_A_9") (class "Default")
      (node (ref "J30") (pin "2") (pinfunction "2_2") (pintype "passive"))
      (node (ref "R604") (pin "1") (pinfunction "1_1") (pintype "passive"))
    )
    (net (code "67") (name "SOLENOID_A_10") (class "Default")
      (node (ref "J30") (pin "4") (pinfunction "4_4") (pintype "passive"))
      (node (ref "R605") (pin "1") (pinfunction "1_1") (pintype "passive"))
    )
    (net (code "68") (name "SOLENOID_A_11") (class "Default")
      (node (ref "J30") (pin "6") (pinfunction "6_6") (pintype "passive"))
      (node (ref "R611") (pin "1") (pinfunction "1_1") (pintype "passive"))
    )
    (net (code "69") (name "SOLENOID_A_12") (class "Default")
      (node (ref "J30") (pin "8") (pinfunction "8_8") (pintype "passive"))
      (node (ref "R606") (pin "1") (pinfunction "1_1") (pintype "passive"))
    )
    (net (code "70") (name "SOLENOID_A_13") (class "Default")
      (node (ref "J33") (pin "2") (pinfunction "2_2") (pintype "passive"))
      (node (ref "R607") (pin "1") (pinfunction "1_1") (pintype "passive"))
    )
    (net (code "71") (name "SOLENOID_A_14") (class "Default")
      (node (ref "J33") (pin "4") (pinfunction "4_4") (pintype "passive"))
      (node (ref "R608") (pin "1") (pinfunction "1_1") (pintype "passive"))
    )
    (net (code "72") (name "SOLENOID_A_15") (class "Default")
      (node (ref "J33") (pin "6") (pinfunction "6_6") (pintype "passive"))
      (node (ref "R609") (pin "1") (pinfunction "1_1") (pintype "passive"))
    )
    (net (code "73") (name "SOLENOID_A_16") (class "Default")
      (node (ref "J33") (pin "8") (pinfunction "8_8") (pintype "passive"))
      (node (ref "R610") (pin "1") (pinfunction "1_1") (pintype "passive"))
    )
    (net (code "74") (name "SOLENOID_CTR_1") (class "Default")
      (node (ref "R479") (pin "2") (pinfunction "2_2") (pintype "passive"))
      (node (ref "U48") (pin "11") (pinfunction "P07_11") (pintype "passive"))
    )
    (net (code "75") (name "SOLENOID_CTR_2") (class "Default")
      (node (ref "R480") (pin "2") (pinfunction "2_2") (pintype "passive"))
      (node (ref "U48") (pin "17") (pinfunction "P14_17") (pintype "passive"))
    )
    (net (code "76") (name "SOLENOID_CTR_3") (class "Default")
      (node (ref "R481") (pin "2") (pinfunction "2_2") (pintype "passive"))
      (node (ref "U48") (pin "9") (pinfunction "P05_9") (pintype "passive"))
    )
    (net (code "77") (name "SOLENOID_CTR_4") (class "Default")
      (node (ref "R482") (pin "2") (pinfunction "2_2") (pintype "passive"))
      (node (ref "U48") (pin "18") (pinfunction "P15_18") (pintype "passive"))
    )
    (net (code "78") (name "SOLENOID_CTR_5") (class "Default")
      (node (ref "R487") (pin "2") (pinfunction "2_2") (pintype "passive"))
      (node (ref "U48") (pin "6") (pinfunction "P02_6") (pintype "passive"))
    )
    (net (code "79") (name "SOLENOID_CTR_6") (class "Default")
      (node (ref "R488") (pin "2") (pinfunction "2_2") (pintype "passive"))
      (node (ref "U48") (pin "16") (pinfunction "P13_16") (pintype "passive"))
    )
    (net (code "80") (name "SOLENOID_CTR_7") (class "Default")
      (node (ref "R489") (pin "2") (pinfunction "2_2") (pintype "passive"))
      (node (ref "U48") (pin "4") (pinfunction "P00_4") (pintype "passive"))
    )
    (net (code "81") (name "SOLENOID_CTR_8") (class "Default")
      (node (ref "R490") (pin "2") (pinfunction "2_2") (pintype "passive"))
      (node (ref "U48") (pin "14") (pinfunction "P11_14") (pintype "passive"))
    )
    (net (code "82") (name "SOLENOID_CTR_9") (class "Default")
      (node (ref "R495") (pin "2") (pinfunction "2_2") (pintype "passive"))
      (node (ref "U48") (pin "5") (pinfunction "P01_5") (pintype "passive"))
    )
    (net (code "83") (name "SOLENOID_CTR_10") (class "Default")
      (node (ref "R496") (pin "2") (pinfunction "2_2") (pintype "passive"))
      (node (ref "U48") (pin "13") (pinfunction "P10_13") (pintype "passive"))
    )
    (net (code "84") (name "SOLENOID_CTR_11") (class "Default")
      (node (ref "R497") (pin "2") (pinfunction "2_2") (pintype "passive"))
      (node (ref "U48") (pin "7") (pinfunction "P03_7") (pintype "passive"))
    )
    (net (code "85") (name "SOLENOID_CTR_12") (class "Default")
      (node (ref "R498") (pin "2") (pinfunction "2_2") (pintype "passive"))
      (node (ref "U48") (pin "15") (pinfunction "P12_15") (pintype "passive"))
    )
    (net (code "86") (name "SOLENOID_CTR_13") (class "Default")
      (node (ref "R508") (pin "2") (pinfunction "2_2") (pintype "passive"))
      (node (ref "U48") (pin "8") (pinfunction "P04_8") (pintype "passive"))
    )
    (net (code "87") (name "SOLENOID_CTR_14") (class "Default")
      (node (ref "R509") (pin "2") (pinfunction "2_2") (pintype "passive"))
      (node (ref "U48") (pin "19") (pinfunction "P16_19") (pintype "passive"))
    )
    (net (code "88") (name "SOLENOID_CTR_15") (class "Default")
      (node (ref "R510") (pin "2") (pinfunction "2_2") (pintype "passive"))
      (node (ref "U48") (pin "10") (pinfunction "P06_10") (pintype "passive"))
    )
    (net (code "89") (name "SOLENOID_CTR_16") (class "Default")
      (node (ref "R511") (pin "2") (pinfunction "2_2") (pintype "passive"))
      (node (ref "U48") (pin "20") (pinfunction "P17_20") (pintype "passive"))
    )
  )
)
